# Motor_Driver.net
KiCad netlist of a schematic drawn in Altium Designer
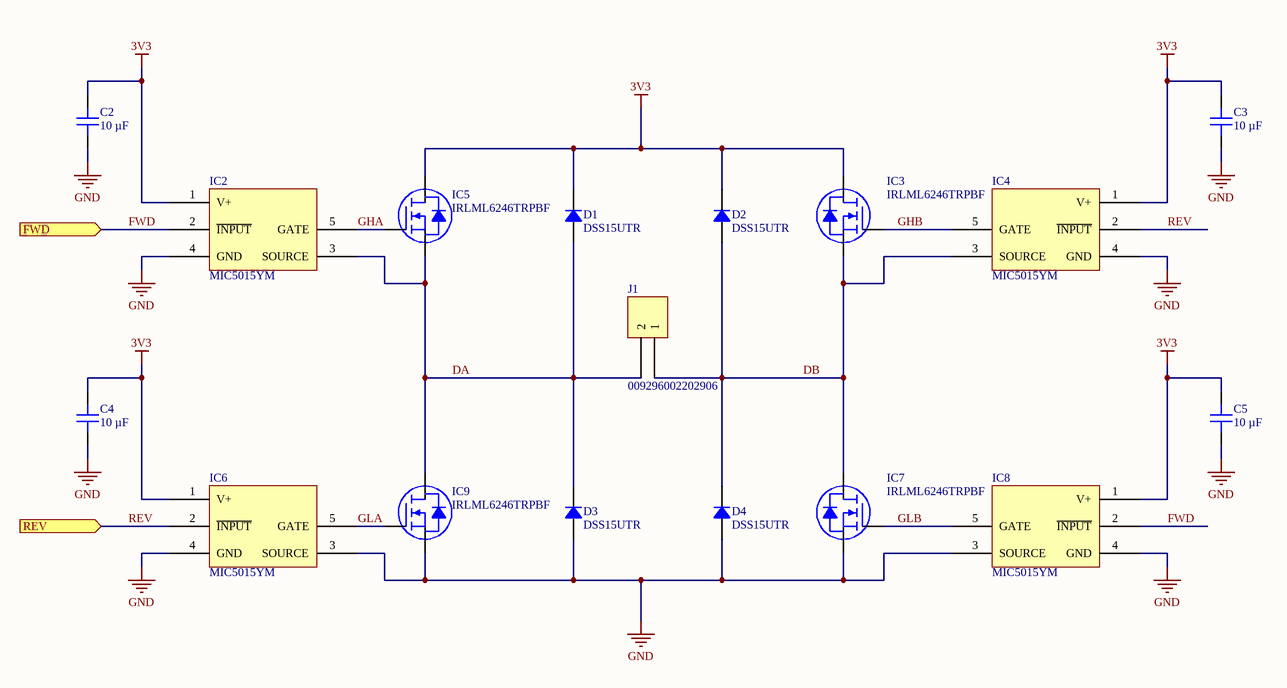
[diagram p0: Motor Driver.SchDoc]

(export (version "E")
  (design (tool "Eeschema 10.0.6"))
  (components
    (comp (ref "C2")
      (value "10 µF")
      (footprint "CAP 1210_3225 - 1MM")
      (description "CAP CER 10UF 16V X5R 1210")
      (fields
        (field (name "PART NUMBER") "CL32A106MOJNNNE")
        (field (name "MANUFACTURER") "Samsung Electro-Mechanics")
      )
      (libsource (lib "altiumlibrary.com") (part "Capacitor"))
    )
    (comp (ref "C3")
      (value "10 µF")
      (footprint "CAP 1210_3225 - 1MM")
      (description "CAP CER 10UF 16V X5R 1210")
      (fields
        (field (name "PART NUMBER") "CL32A106MOJNNNE")
        (field (name "MANUFACTURER") "Samsung Electro-Mechanics")
      )
      (libsource (lib "altiumlibrary.com") (part "Capacitor"))
    )
    (comp (ref "C4")
      (value "10 µF")
      (footprint "CAP 1210_3225 - 1MM")
      (description "CAP CER 10UF 16V X5R 1210")
      (fields
        (field (name "PART NUMBER") "CL32A106MOJNNNE")
        (field (name "MANUFACTURER") "Samsung Electro-Mechanics")
      )
      (libsource (lib "altiumlibrary.com") (part "Capacitor"))
    )
    (comp (ref "C5")
      (value "10 µF")
      (footprint "CAP 1210_3225 - 1MM")
      (description "CAP CER 10UF 16V X5R 1210")
      (fields
        (field (name "PART NUMBER") "CL32A106MOJNNNE")
        (field (name "MANUFACTURER") "Samsung Electro-Mechanics")
      )
      (libsource (lib "altiumlibrary.com") (part "Capacitor"))
    )
    (comp (ref "D1")
      (value "DSS15UTR")
      (footprint "SOD123F")
      (description "SCHOTTKY 50V SOD-123FL")
      (fields (field (name "MANUFACTURER") "SMC Diode Solutions"))
      (libsource (lib "altiumlibrary.com") (part "Diode"))
    )
    (comp (ref "D2")
      (value "DSS15UTR")
      (footprint "SOD123F")
      (description "SCHOTTKY 50V SOD-123FL")
      (fields (field (name "MANUFACTURER") "SMC Diode Solutions"))
      (libsource (lib "altiumlibrary.com") (part "Diode"))
    )
    (comp (ref "D3")
      (value "DSS15UTR")
      (footprint "SOD123F")
      (description "SCHOTTKY 50V SOD-123FL")
      (fields (field (name "MANUFACTURER") "SMC Diode Solutions"))
      (libsource (lib "altiumlibrary.com") (part "Diode"))
    )
    (comp (ref "D4")
      (value "DSS15UTR")
      (footprint "SOD123F")
      (description "SCHOTTKY 50V SOD-123FL")
      (fields (field (name "MANUFACTURER") "SMC Diode Solutions"))
      (libsource (lib "altiumlibrary.com") (part "Diode"))
    )
    (comp (ref "IC2")
      (value "MIC5015YM")
      (footprint "MICROCHIP MICREL SOP-8 M")
      (description "IC GATE DRVR HI/LOW SIDE 8SOIC")
      (fields (field (name "MANUFACTURER") "Microchip Technology"))
      (libsource (lib "altiumlibrary.com") (part "MICROCHIP MIC5015"))
    )
    (comp (ref "IC3")
      (value "IRLML6246TRPBF")
      (footprint "INFINEON SOT-23-3")
      (description "MOSFET N-CH 20V 4.1A SOT-23")
      (fields (field (name "MANUFACTURER") "Infineon Technologies"))
      (libsource (lib "") (part "INFINEON MOSFET N-CH SOT-23-3 GSD_1"))
    )
    (comp (ref "IC4")
      (value "MIC5015YM")
      (footprint "MICROCHIP MICREL SOP-8 M")
      (description "IC GATE DRVR HI/LOW SIDE 8SOIC")
      (fields (field (name "MANUFACTURER") "Microchip Technology"))
      (libsource (lib "") (part "MICROCHIP MIC5015_1"))
    )
    (comp (ref "IC5")
      (value "IRLML6246TRPBF")
      (footprint "INFINEON SOT-23-3")
      (description "MOSFET N-CH 20V 4.1A SOT-23")
      (fields (field (name "MANUFACTURER") "Infineon Technologies"))
      (libsource (lib "altiumlibrary.com") (part "INFINEON MOSFET N-CH SOT-23-3 GSD"))
    )
    (comp (ref "IC6")
      (value "MIC5015YM")
      (footprint "MICROCHIP MICREL SOP-8 M")
      (description "IC GATE DRVR HI/LOW SIDE 8SOIC")
      (fields (field (name "MANUFACTURER") "Microchip Technology"))
      (libsource (lib "altiumlibrary.com") (part "MICROCHIP MIC5015"))
    )
    (comp (ref "IC7")
      (value "IRLML6246TRPBF")
      (footprint "INFINEON SOT-23-3")
      (description "MOSFET N-CH 20V 4.1A SOT-23")
      (fields (field (name "MANUFACTURER") "Infineon Technologies"))
      (libsource (lib "") (part "INFINEON MOSFET N-CH SOT-23-3 GSD_1"))
    )
    (comp (ref "IC8")
      (value "MIC5015YM")
      (footprint "MICROCHIP MICREL SOP-8 M")
      (description "IC GATE DRVR HI/LOW SIDE 8SOIC")
      (fields (field (name "MANUFACTURER") "Microchip Technology"))
      (libsource (lib "") (part "MICROCHIP MIC5015_1"))
    )
    (comp (ref "IC9")
      (value "IRLML6246TRPBF")
      (footprint "INFINEON SOT-23-3")
      (description "MOSFET N-CH 20V 4.1A SOT-23")
      (fields (field (name "MANUFACTURER") "Infineon Technologies"))
      (libsource (lib "altiumlibrary.com") (part "INFINEON MOSFET N-CH SOT-23-3 GSD"))
    )
    (comp (ref "J1")
      (value "009296002202906")
      (footprint "AVX 9296002202806")
      (description "CONN WIRE POKE-IN 2POS SMD RA")
      (fields (field (name "MANUFACTURER") "AVX Corporation"))
      (libsource (lib "altiumlibrary.com") (part "2 Pin"))
    )
  )
  (nets
    (net (code "1") (name "/DA") (class "Default")
      (node (ref "D1") (pin "1") (pinfunction "1_1") (pintype "passive"))
      (node (ref "D3") (pin "2") (pinfunction "2_2") (pintype "passive"))
      (node (ref "IC2") (pin "3") (pinfunction "SOURCE_3") (pintype "passive"))
      (node (ref "IC5") (pin "2") (pinfunction "S_2") (pintype "passive"))
      (node (ref "IC9") (pin "3") (pinfunction "D_3") (pintype "passive"))
      (node (ref "J1") (pin "2") (pinfunction "2_2") (pintype "passive"))
    )
    (net (code "2") (name "/DB") (class "Default")
      (node (ref "D2") (pin "1") (pinfunction "1_1") (pintype "passive"))
      (node (ref "D4") (pin "2") (pinfunction "2_2") (pintype "passive"))
      (node (ref "IC3") (pin "2") (pinfunction "S_2") (pintype "passive"))
      (node (ref "IC4") (pin "3") (pinfunction "SOURCE_3") (pintype "passive"))
      (node (ref "IC7") (pin "3") (pinfunction "D_3") (pintype "passive"))
      (node (ref "J1") (pin "1") (pinfunction "1_1") (pintype "passive"))
    )
    (net (code "3") (name "/FWD") (class "Default")
      (node (ref "IC2") (pin "2") (pinfunction "~{INPUT}_2") (pintype "passive"))
      (node (ref "IC8") (pin "2") (pinfunction "~{INPUT}_2") (pintype "passive"))
    )
    (net (code "4") (name "/GHA") (class "Default")
      (node (ref "IC2") (pin "5") (pinfunction "GATE_5") (pintype "passive"))
      (node (ref "IC5") (pin "1") (pinfunction "G_1") (pintype "passive"))
    )
    (net (code "5") (name "/GHB") (class "Default")
      (node (ref "IC3") (pin "1") (pinfunction "G_1") (pintype "passive"))
      (node (ref "IC4") (pin "5") (pinfunction "GATE_5") (pintype "passive"))
    )
    (net (code "6") (name "/GLA") (class "Default")
      (node (ref "IC6") (pin "5") (pinfunction "GATE_5") (pintype "passive"))
      (node (ref "IC9") (pin "1") (pinfunction "G_1") (pintype "passive"))
    )
    (net (code "7") (name "/GLB") (class "Default")
      (node (ref "IC7") (pin "1") (pinfunction "G_1") (pintype "passive"))
      (node (ref "IC8") (pin "5") (pinfunction "GATE_5") (pintype "passive"))
    )
    (net (code "8") (name "/REV") (class "Default")
      (node (ref "IC4") (pin "2") (pinfunction "~{INPUT}_2") (pintype "passive"))
      (node (ref "IC6") (pin "2") (pinfunction "~{INPUT}_2") (pintype "passive"))
    )
    (net (code "9") (name "3V3") (class "Default")
      (node (ref "C2") (pin "2") (pinfunction "2_2") (pintype "passive"))
      (node (ref "C3") (pin "2") (pinfunction "2_2") (pintype "passive"))
      (node (ref "C4") (pin "2") (pinfunction "2_2") (pintype "passive"))
      (node (ref "C5") (pin "2") (pinfunction "2_2") (pintype "passive"))
      (node (ref "D1") (pin "2") (pinfunction "2_2") (pintype "passive"))
      (node (ref "D2") (pin "2") (pinfunction "2_2") (pintype "passive"))
      (node (ref "IC2") (pin "1") (pinfunction "V+_1") (pintype "passive"))
      (node (ref "IC3") (pin "3") (pinfunction "D_3") (pintype "passive"))
      (node (ref "IC4") (pin "1") (pinfunction "V+_1") (pintype "passive"))
      (node (ref "IC5") (pin "3") (pinfunction "D_3") (pintype "passive"))
      (node (ref "IC6") (pin "1") (pinfunction "V+_1") (pintype "passive"))
      (node (ref "IC8") (pin "1") (pinfunction "V+_1") (pintype "passive"))
    )
    (net (code "10") (name "GND") (class "Default")
      (node (ref "C2") (pin "1") (pinfunction "1_1") (pintype "passive"))
      (node (ref "C3") (pin "1") (pinfunction "1_1") (pintype "passive"))
      (node (ref "C4") (pin "1") (pinfunction "1_1") (pintype "passive"))
      (node (ref "C5") (pin "1") (pinfunction "1_1") (pintype "passive"))
      (node (ref "D3") (pin "1") (pinfunction "1_1") (pintype "passive"))
      (node (ref "D4") (pin "1") (pinfunction "1_1") (pintype "passive"))
      (node (ref "IC2") (pin "4") (pinfunction "GND_4") (pintype "passive"))
      (node (ref "IC4") (pin "4") (pinfunction "GND_4") (pintype "passive"))
      (node (ref "IC6") (pin "3") (pinfunction "SOURCE_3") (pintype "passive"))
      (node (ref "IC6") (pin "4") (pinfunction "GND_4") (pintype "passive"))
      (node (ref "IC7") (pin "2") (pinfunction "S_2") (pintype "passive"))
      (node (ref "IC8") (pin "3") (pinfunction "SOURCE_3") (pintype "passive"))
      (node (ref "IC8") (pin "4") (pinfunction "GND_4") (pintype "passive"))
      (node (ref "IC9") (pin "2") (pinfunction "S_2") (pintype "passive"))
    )
  )
)
